# rigidPCB_rev.net
KiCad netlist of a schematic drawn in Altium Designer
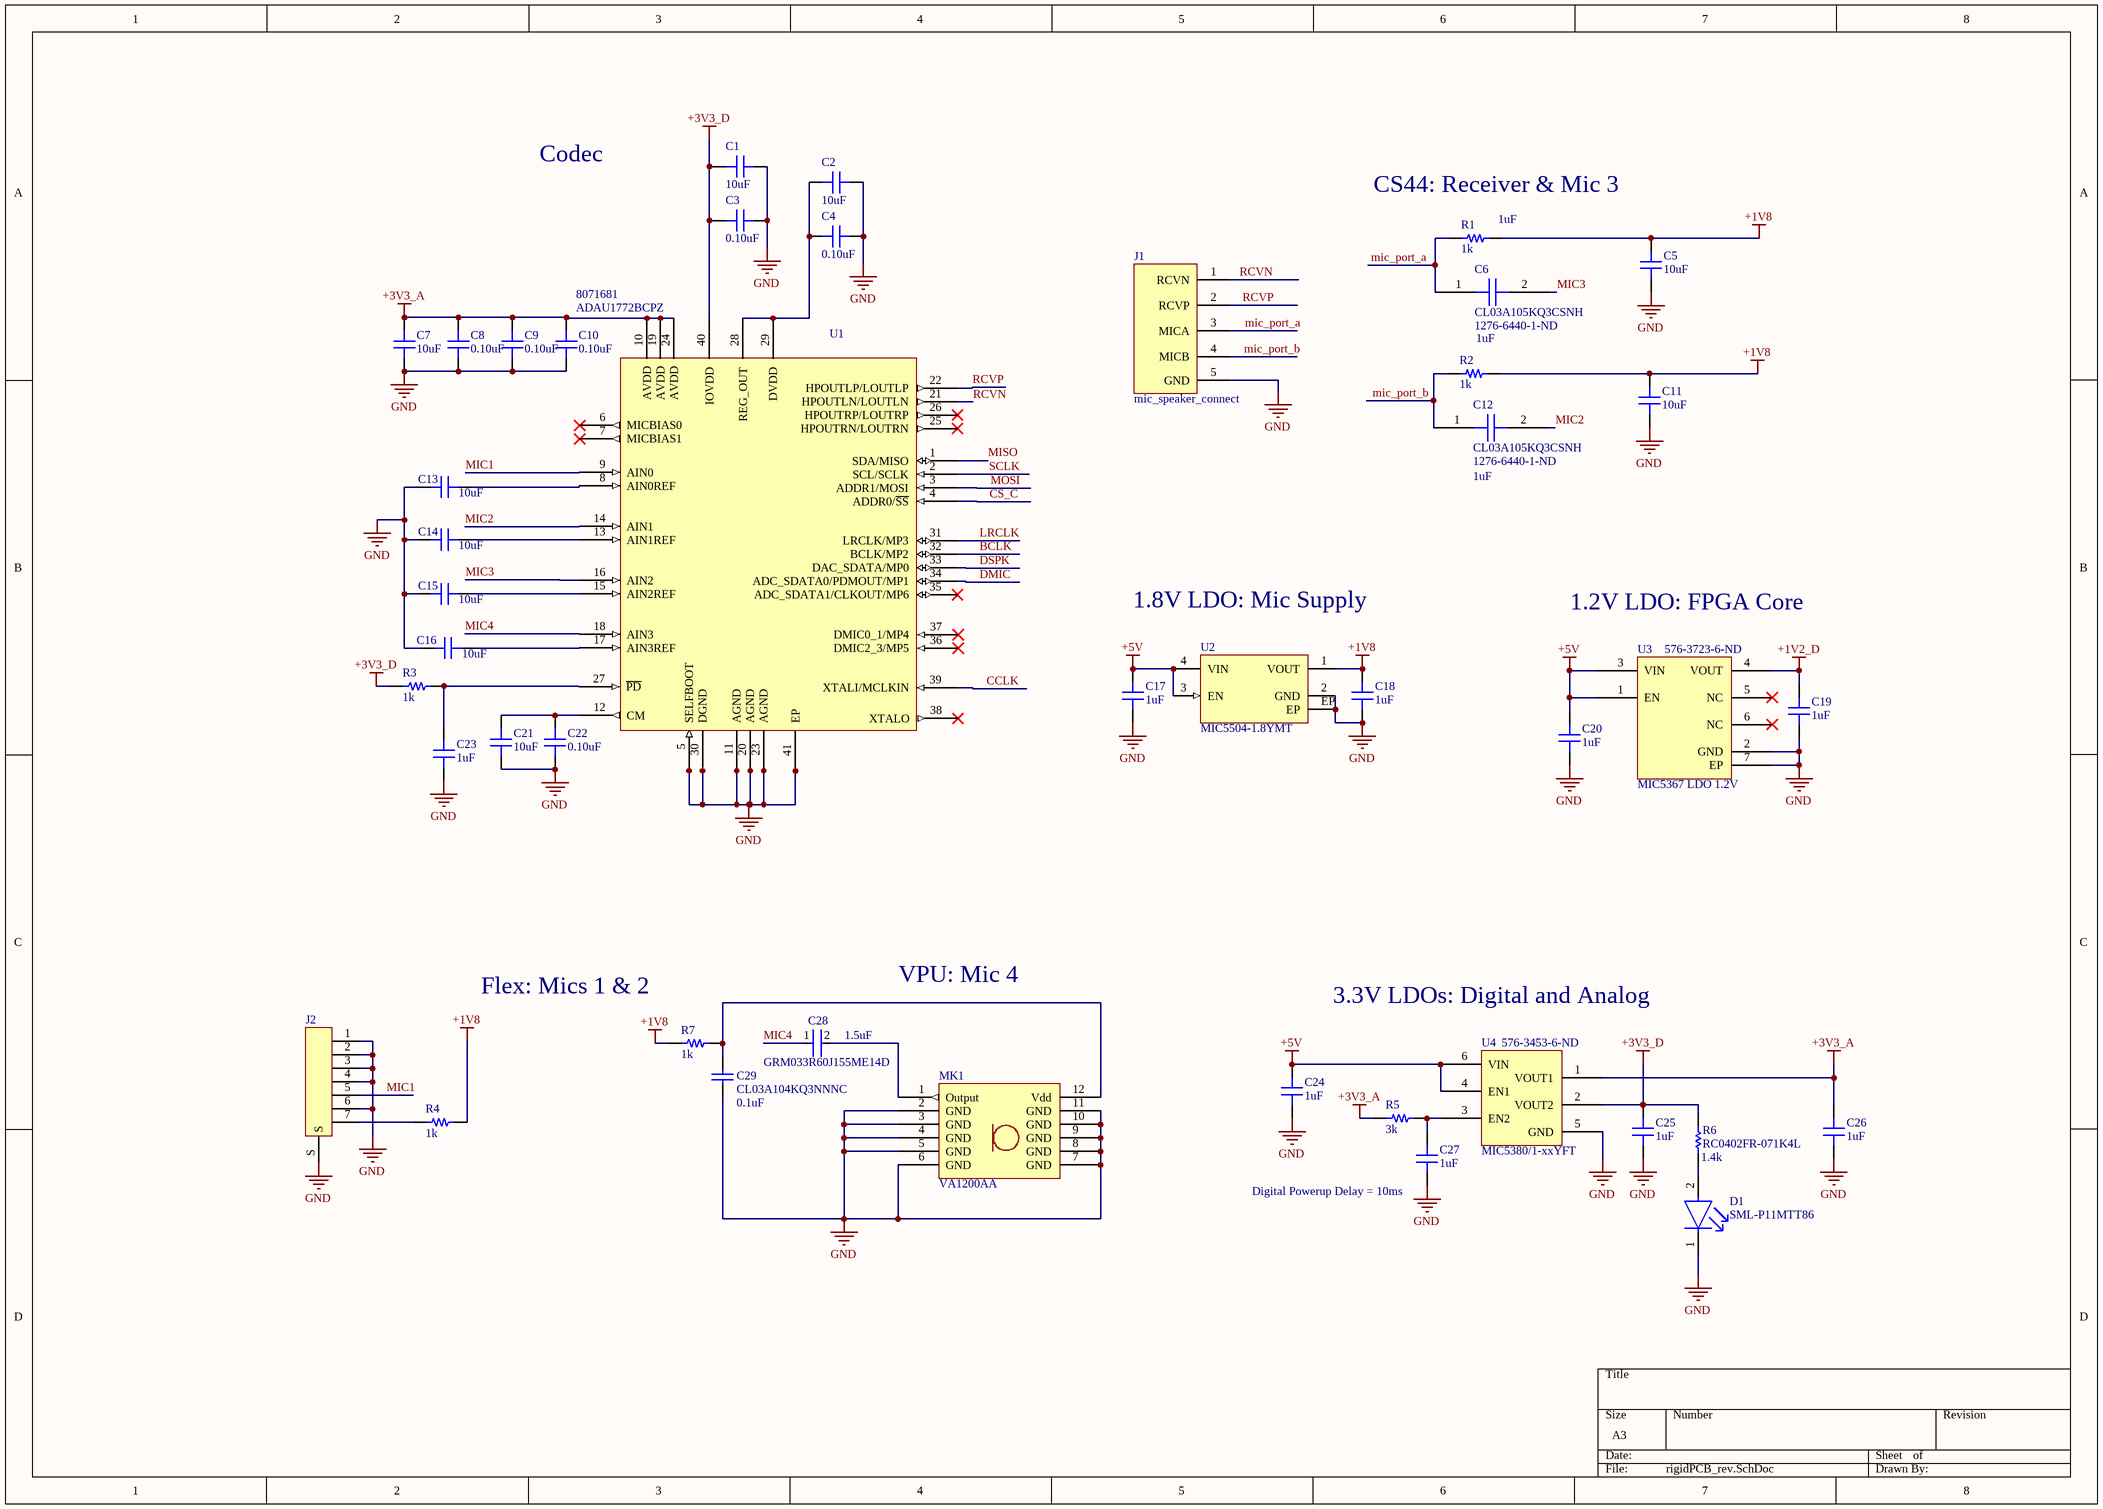
[diagram p0: rigidPCB_rev.SchDoc]

(export (version "E")
  (design (tool "Eeschema 10.0.6"))
  (components
    (comp (ref "C1")
      (value "10uF")
      (footprint "CAP 0402/1005")
      (description "CAP CER 10UF 6.3V X5R 0402")
      (fields
        (field (name "PART NUMBER") "C1005X5R0J106M050BC")
        (field (name "MANUFACTURER") "TDK Corporation")
      )
      (libsource (lib "Celestial Library Database") (part "Capacitor"))
    )
    (comp (ref "C2")
      (value "10uF")
      (footprint "CAP 0402/1005")
      (description "CAP CER 10UF 6.3V X5R 0402")
      (fields
        (field (name "PART NUMBER") "C1005X5R0J106M050BC")
        (field (name "MANUFACTURER") "TDK Corporation")
      )
      (libsource (lib "Celestial Library Database") (part "Capacitor"))
    )
    (comp (ref "C3")
      (value "0.10uF")
      (footprint "CAP 0201/0603")
      (description "CAP CER 0.1UF 10V X5R 0201")
      (fields
        (field (name "PART NUMBER") "CL03A104KP3NNNC")
        (field (name "MANUFACTURER") "Samsung Electro-Mechanics America, Inc.")
      )
      (libsource (lib "Celestial Library Database") (part "Capacitor"))
    )
    (comp (ref "C4")
      (value "0.10uF")
      (footprint "CAP 0201/0603")
      (description "CAP CER 0.1UF 10V X5R 0201")
      (fields
        (field (name "PART NUMBER") "CL03A104KP3NNNC")
        (field (name "MANUFACTURER") "Samsung Electro-Mechanics America, Inc.")
      )
      (libsource (lib "Celestial Library Database") (part "Capacitor"))
    )
    (comp (ref "C5")
      (value "10uF")
      (footprint "CAP 0402/1005")
      (description "CAP CER 10UF 6.3V X5R 0402")
      (fields
        (field (name "PART NUMBER") "C1005X5R0J106M050BC")
        (field (name "MANUFACTURER") "TDK Corporation")
      )
      (libsource (lib "Celestial Library Database") (part "Capacitor"))
    )
    (comp (ref "C6")
      (value "CL03A105KQ3CSNH")
      (footprint "CL03A105KQ3CSNH")
      (description "1 µF ±10% 6.3V Ceramic Capacitor X5R 0201 (0603 Metric)")
      (fields (field (name "SUPPLIER PART NUMBER 1") "1276-6440-1-ND"))
      (libsource (lib "OSP_DJB_Rigid") (part "CL03A105KQ3CSNH"))
    )
    (comp (ref "C7")
      (value "10uF")
      (footprint "CAP 0402/1005")
      (description "CAP CER 10UF 6.3V X5R 0402")
      (fields
        (field (name "PART NUMBER") "C1005X5R0J106M050BC")
        (field (name "MANUFACTURER") "TDK Corporation")
      )
      (libsource (lib "Celestial Library Database") (part "Capacitor"))
    )
    (comp (ref "C8")
      (value "0.10uF")
      (footprint "CAP 0201/0603")
      (description "CAP CER 0.1UF 10V X5R 0201")
      (fields
        (field (name "PART NUMBER") "CL03A104KP3NNNC")
        (field (name "MANUFACTURER") "Samsung Electro-Mechanics America, Inc.")
      )
      (libsource (lib "Celestial Library Database") (part "Capacitor"))
    )
    (comp (ref "C9")
      (value "0.10uF")
      (footprint "CAP 0201/0603")
      (description "CAP CER 0.1UF 10V X5R 0201")
      (fields
        (field (name "PART NUMBER") "CL03A104KP3NNNC")
        (field (name "MANUFACTURER") "Samsung Electro-Mechanics America, Inc.")
      )
      (libsource (lib "Celestial Library Database") (part "Capacitor"))
    )
    (comp (ref "C10")
      (value "0.10uF")
      (footprint "CAP 0201/0603")
      (description "CAP CER 0.1UF 10V X5R 0201")
      (fields
        (field (name "PART NUMBER") "CL03A104KP3NNNC")
        (field (name "MANUFACTURER") "Samsung Electro-Mechanics America, Inc.")
      )
      (libsource (lib "Celestial Library Database") (part "Capacitor"))
    )
    (comp (ref "C11")
      (value "10uF")
      (footprint "CAP 0402/1005")
      (description "CAP CER 10UF 6.3V X5R 0402")
      (fields
        (field (name "PART NUMBER") "C1005X5R0J106M050BC")
        (field (name "MANUFACTURER") "TDK Corporation")
      )
      (libsource (lib "Celestial Library Database") (part "Capacitor"))
    )
    (comp (ref "C12")
      (value "CL03A105KQ3CSNH")
      (footprint "CL03A105KQ3CSNH")
      (description "1 µF ±10% 6.3V Ceramic Capacitor X5R 0201 (0603 Metric)")
      (fields (field (name "SUPPLIER PART NUMBER 1") "1276-6440-1-ND"))
      (libsource (lib "OSP_DJB_Rigid") (part "CL03A105KQ3CSNH"))
    )
    (comp (ref "C13")
      (value "10uF")
      (footprint "CAP 0402/1005")
      (description "CAP CER 10UF 6.3V X5R 0402")
      (fields
        (field (name "PART NUMBER") "C1005X5R0J106M050BC")
        (field (name "MANUFACTURER") "TDK Corporation")
      )
      (libsource (lib "Celestial Library Database") (part "Capacitor"))
    )
    (comp (ref "C14")
      (value "10uF")
      (footprint "CAP 0402/1005")
      (description "CAP CER 10UF 6.3V X5R 0402")
      (fields
        (field (name "PART NUMBER") "C1005X5R0J106M050BC")
        (field (name "MANUFACTURER") "TDK Corporation")
      )
      (libsource (lib "Celestial Library Database") (part "Capacitor"))
    )
    (comp (ref "C15")
      (value "10uF")
      (footprint "CAP 0402/1005")
      (description "CAP CER 10UF 6.3V X5R 0402")
      (fields
        (field (name "PART NUMBER") "C1005X5R0J106M050BC")
        (field (name "MANUFACTURER") "TDK Corporation")
      )
      (libsource (lib "Celestial Library Database") (part "Capacitor"))
    )
    (comp (ref "C16")
      (value "10uF")
      (footprint "CAP 0402/1005")
      (description "CAP CER 10UF 6.3V X5R 0402")
      (fields
        (field (name "PART NUMBER") "C1005X5R0J106M050BC")
        (field (name "MANUFACTURER") "TDK Corporation")
      )
      (libsource (lib "Celestial Library Database") (part "Capacitor"))
    )
    (comp (ref "C17")
      (value "1uF")
      (footprint "CAP 0201/0603")
      (description "CAP CER 1UF 6.3V X5R 0201")
      (fields (field (name "PART NUMBER") "02016D105MAT2A") (field (name "MANUFACTURER") "AVX Corporation"))
      (libsource (lib "Celestial Library Database") (part "Capacitor"))
    )
    (comp (ref "C18")
      (value "1uF")
      (footprint "CAP 0201/0603")
      (description "CAP CER 1UF 6.3V X5R 0201")
      (fields (field (name "PART NUMBER") "02016D105MAT2A") (field (name "MANUFACTURER") "AVX Corporation"))
      (libsource (lib "Celestial Library Database") (part "Capacitor"))
    )
    (comp (ref "C19")
      (value "1uF")
      (footprint "CAP 0201/0603")
      (description "CAP CER 1UF 6.3V X5R 0201")
      (fields (field (name "PART NUMBER") "02016D105MAT2A") (field (name "MANUFACTURER") "AVX Corporation"))
      (libsource (lib "Celestial Library Database") (part "Capacitor"))
    )
    (comp (ref "C20")
      (value "1uF")
      (footprint "CAP 0201/0603")
      (description "CAP CER 1UF 6.3V X5R 0201")
      (fields (field (name "PART NUMBER") "02016D105MAT2A") (field (name "MANUFACTURER") "AVX Corporation"))
      (libsource (lib "Celestial Library Database") (part "Capacitor"))
    )
    (comp (ref "C21")
      (value "10uF")
      (footprint "CAP 0402/1005")
      (description "CAP CER 10UF 6.3V X5R 0402")
      (fields
        (field (name "PART NUMBER") "C1005X5R0J106M050BC")
        (field (name "MANUFACTURER") "TDK Corporation")
      )
      (libsource (lib "Celestial Library Database") (part "Capacitor"))
    )
    (comp (ref "C22")
      (value "0.10uF")
      (footprint "CAP 0201/0603")
      (description "CAP CER 0.1UF 10V X5R 0201")
      (fields
        (field (name "PART NUMBER") "CL03A104KP3NNNC")
        (field (name "MANUFACTURER") "Samsung Electro-Mechanics America, Inc.")
      )
      (libsource (lib "Celestial Library Database") (part "Capacitor"))
    )
    (comp (ref "C23")
      (value "1uF")
      (footprint "CAP 0201/0603")
      (description "CAP CER 1UF 6.3V X5R 0201")
      (fields (field (name "PART NUMBER") "02016D105MAT2A") (field (name "MANUFACTURER") "AVX Corporation"))
      (libsource (lib "Celestial Library Database") (part "Capacitor"))
    )
    (comp (ref "C24")
      (value "1uF")
      (footprint "CAP 0201/0603")
      (description "CAP CER 1UF 6.3V X5R 0201")
      (fields (field (name "PART NUMBER") "02016D105MAT2A") (field (name "MANUFACTURER") "AVX Corporation"))
      (libsource (lib "Celestial Library Database") (part "Capacitor"))
    )
    (comp (ref "C25")
      (value "1uF")
      (footprint "CAP 0201/0603")
      (description "CAP CER 1UF 6.3V X5R 0201")
      (fields (field (name "PART NUMBER") "02016D105MAT2A") (field (name "MANUFACTURER") "AVX Corporation"))
      (libsource (lib "Celestial Library Database") (part "Capacitor"))
    )
    (comp (ref "C26")
      (value "1uF")
      (footprint "CAP 0201/0603")
      (description "CAP CER 1UF 6.3V X5R 0201")
      (fields (field (name "PART NUMBER") "02016D105MAT2A") (field (name "MANUFACTURER") "AVX Corporation"))
      (libsource (lib "Celestial Library Database") (part "Capacitor"))
    )
    (comp (ref "C27")
      (value "1uF")
      (footprint "CAP 0201/0603")
      (description "CAP CER 1UF 6.3V X5R 0201")
      (fields (field (name "PART NUMBER") "02016D105MAT2A") (field (name "MANUFACTURER") "AVX Corporation"))
      (libsource (lib "Celestial Library Database") (part "Capacitor"))
    )
    (comp (ref "C28")
      (value "GRM033R60J155ME14D")
      (footprint "FP-GRM033-0_03-IPC_B")
      (description "Chip Multilayer Ceramic Capacitors for General Purpose, 0201, 1.5uF, X5R, 15%, 20%, 6.3V")
      (fields (field (name "TOLERANCE") "20%"))
      (libsource (lib "Altium Content Vault") (part "b4654b650e69147ec39a6b967a45e02"))
    )
    (comp (ref "C29")
      (value "CL03A104KQ3NNNC")
      (footprint "CAPC0603X33X15ML03T05")
      (fields (field (name "MANUFACTURER") "Samsung"))
      (libsource (lib "Altium Content Vault") (part "CAP"))
    )
    (comp (ref "D1")
      (value "SML-P11MTT86")
      (footprint "FP-SML-P11MTT86-MFG")
      (description "LED YELLOW/GREEN CLEAR 1006 SMD")
      (libsource (lib "Altium Content Vault") (part "8706943c75ba83719d021d2fdc84c58"))
    )
    (comp (ref "J1")
      (value "mic_speaker_connect")
      (description "connector to integrated microphone and speaker")
      (libsource (lib "OSP_DJB_Rigid") (part "mic_speaker_connect"))
    )
    (comp (ref "J2")
      (value "FFC")
      (footprint "HIROSE_FH58M-7S-0.25SHW-99")
      (description "Hirose FH58M-7S-0.25SHW(99) 7-pin Top+Bottom Contact FFC Connector")
      (libsource (lib "OSP_Symbols") (part "HIROSE_FH58M-7S-0.25SHW-99"))
    )
    (comp (ref "MK1")
      (value "VA1200AA")
      (footprint "VA1200AA")
      (description "Bone Conductor Sensor Accelerometer")
      (libsource (lib "OSP_DJB_Rigid") (part "VA1200AA"))
    )
    (comp (ref "R1")
      (value "1k")
      (footprint "RES 0201/0603")
      (description "RES SMD 1K OHM 5% 1/20W 0201")
      (fields (field (name "PART NUMBER") "RC0201JR-071KL") (field (name "MANUFACTURER") "Yageo"))
      (libsource (lib "Celestial Library Database") (part "Resistor"))
    )
    (comp (ref "R2")
      (value "1k")
      (footprint "RES 0201/0603")
      (description "RES SMD 1K OHM 5% 1/20W 0201")
      (fields (field (name "PART NUMBER") "RC0201JR-071KL") (field (name "MANUFACTURER") "Yageo"))
      (libsource (lib "Celestial Library Database") (part "Resistor"))
    )
    (comp (ref "R3")
      (value "1k")
      (footprint "RES 0201/0603")
      (description "RES SMD 1K OHM 5% 1/20W 0201")
      (fields (field (name "PART NUMBER") "RC0201JR-071KL") (field (name "MANUFACTURER") "Yageo"))
      (libsource (lib "Celestial Library Database") (part "Resistor"))
    )
    (comp (ref "R4")
      (value "1k")
      (footprint "RES 0201/0603")
      (description "RES SMD 1K OHM 5% 1/20W 0201")
      (fields (field (name "PART NUMBER") "RC0201JR-071KL") (field (name "MANUFACTURER") "Yageo"))
      (libsource (lib "Celestial Library Database") (part "Resistor"))
    )
    (comp (ref "R5")
      (value "3k")
      (footprint "RES 0201/0603")
      (description "RES SMD 3K OHM 1% 1/20W 0201")
      (fields (field (name "PART NUMBER") "RC0201FR-073KL") (field (name "MANUFACTURER") "Yageo"))
      (libsource (lib "Celestial Library Database") (part "Resistor"))
    )
    (comp (ref "R6")
      (value "RC0402FR-071K4L")
      (footprint "RESC1005X40X25NL05T10")
      (fields (field (name "MANUFACTURER") "Yageo / Phycomp"))
      (libsource (lib "Altium Content Vault") (part "RES"))
    )
    (comp (ref "R7")
      (value "1k")
      (footprint "RES 0201/0603")
      (description "RES SMD 1K OHM 5% 1/20W 0201")
      (fields (field (name "PART NUMBER") "RC0201JR-071KL") (field (name "MANUFACTURER") "Yageo"))
      (libsource (lib "Celestial Library Database") (part "Resistor"))
    )
    (comp (ref "U1")
      (value "~")
      (footprint "ADAU1772BCPZ")
      (description "General Purpose Audio Codec 4ADC / 2DAC Ch 40-Pin LFCSP")
      (fields
        (field (name "SUPPLIER PART NUMBER 1") "ADAU1772BCPZ")
        (field (name "SUPPLIER PART NUMBER 2") "8071681")
      )
      (libsource (lib "OSP_DJB_Rigid") (part "ADAU1772BCPZ"))
    )
    (comp (ref "U2")
      (value "MIC5504-1.8YMT")
      (footprint "MICREL_DFN4")
      (description "Micrel MIC5504-1.8YMT 1.8V 300mA LDO")
      (libsource (lib "OSP_Symbols") (part "MICREL_MIC5504-1.8YMT"))
    )
    (comp (ref "U3")
      (value "MIC5367 LDO 1.2V")
      (footprint "LDO 1.2V")
      (fields (field (name "SUPPLIER PART NUMBER 1") "576-3723-6-ND"))
      (libsource (lib "Mark_Library1") (part "MIC5367 LDO 1.2V"))
    )
    (comp (ref "U4")
      (value "MIC5380/1-xxYFT")
      (footprint "06L FCSTSLP")
      (description "LDO 2fixed Outputs")
      (fields (field (name "SUPPLIER PART NUMBER 1") "576-3453-6-ND"))
      (libsource (lib "Mark_Library1") (part "MIC5380/1-xxYFT"))
    )
  )
  (nets
    (net (code "1") (name "+1V2_D") (class "Default")
      (node (ref "C19") (pin "2") (pinfunction "2_2") (pintype "passive"))
      (node (ref "U3") (pin "4") (pinfunction "VOUT_4") (pintype "passive"))
    )
    (net (code "2") (name "+1V8") (class "Default")
      (node (ref "C11") (pin "2") (pinfunction "2_2") (pintype "passive"))
      (node (ref "C18") (pin "2") (pinfunction "2_2") (pintype "passive"))
      (node (ref "C5") (pin "2") (pinfunction "2_2") (pintype "passive"))
      (node (ref "R1") (pin "2") (pinfunction "2_2") (pintype "passive"))
      (node (ref "R2") (pin "2") (pinfunction "2_2") (pintype "passive"))
      (node (ref "R4") (pin "2") (pinfunction "2_2") (pintype "passive"))
      (node (ref "R7") (pin "1") (pinfunction "1_1") (pintype "passive"))
      (node (ref "U2") (pin "1") (pinfunction "VOUT_1") (pintype "power_in"))
    )
    (net (code "3") (name "+3V3_A") (class "Default")
      (node (ref "C10") (pin "2") (pinfunction "2_2") (pintype "passive"))
      (node (ref "C26") (pin "2") (pinfunction "2_2") (pintype "passive"))
      (node (ref "C7") (pin "1") (pinfunction "1_1") (pintype "passive"))
      (node (ref "C8") (pin "2") (pinfunction "2_2") (pintype "passive"))
      (node (ref "C9") (pin "2") (pinfunction "2_2") (pintype "passive"))
      (node (ref "R5") (pin "1") (pinfunction "1_1") (pintype "passive"))
      (node (ref "U1") (pin "10") (pinfunction "AVDD_10") (pintype "power_in"))
      (node (ref "U1") (pin "19") (pinfunction "AVDD_19") (pintype "power_in"))
      (node (ref "U1") (pin "24") (pinfunction "AVDD_24") (pintype "power_in"))
      (node (ref "U4") (pin "1") (pinfunction "VOUT1_1") (pintype "passive"))
    )
    (net (code "4") (name "+3V3_D") (class "Default")
      (node (ref "C1") (pin "2") (pinfunction "2_2") (pintype "passive"))
      (node (ref "C25") (pin "2") (pinfunction "2_2") (pintype "passive"))
      (node (ref "C3") (pin "1") (pinfunction "1_1") (pintype "passive"))
      (node (ref "R3") (pin "1") (pinfunction "1_1") (pintype "passive"))
      (node (ref "R6") (pin "2") (pinfunction "2_2") (pintype "passive"))
      (node (ref "U1") (pin "40") (pinfunction "IOVDD_40") (pintype "power_in"))
      (node (ref "U4") (pin "2") (pinfunction "VOUT2_2") (pintype "passive"))
    )
    (net (code "5") (name "+5V") (class "Default")
      (node (ref "C17") (pin "2") (pinfunction "2_2") (pintype "passive"))
      (node (ref "C20") (pin "2") (pinfunction "2_2") (pintype "passive"))
      (node (ref "C24") (pin "2") (pinfunction "2_2") (pintype "passive"))
      (node (ref "U2") (pin "3") (pinfunction "EN_3") (pintype "input"))
      (node (ref "U2") (pin "4") (pinfunction "VIN_4") (pintype "power_in"))
      (node (ref "U3") (pin "1") (pinfunction "EN_1") (pintype "passive"))
      (node (ref "U3") (pin "3") (pinfunction "VIN_3") (pintype "passive"))
      (node (ref "U4") (pin "4") (pinfunction "EN1_4") (pintype "passive"))
      (node (ref "U4") (pin "6") (pinfunction "VIN_6") (pintype "passive"))
    )
    (net (code "6") (name "/BCLK") (class "Default")
      (node (ref "U1") (pin "32") (pinfunction "BCLK/MP2_32") (pintype "bidirectional"))
    )
    (net (code "7") (name "/CCLK") (class "Default")
      (node (ref "U1") (pin "39") (pinfunction "XTALI/MCLKIN_39") (pintype "input"))
    )
    (net (code "8") (name "/CS_C") (class "Default")
      (node (ref "U1") (pin "4") (pinfunction "ADDR0/~{SS}_4") (pintype "input"))
    )
    (net (code "9") (name "/DMIC") (class "Default")
      (node (ref "U1") (pin "34") (pinfunction "ADC_SDATA0/PDMOUT/MP1_34") (pintype "bidirectional"))
    )
    (net (code "10") (name "/DSPK") (class "Default")
      (node (ref "U1") (pin "33") (pinfunction "DAC_SDATA/MP0_33") (pintype "bidirectional"))
    )
    (net (code "11") (name "/LRCLK") (class "Default")
      (node (ref "U1") (pin "31") (pinfunction "LRCLK/MP3_31") (pintype "bidirectional"))
    )
    (net (code "12") (name "/MIC1") (class "Default")
      (node (ref "J2") (pin "5") (pintype "passive"))
      (node (ref "U1") (pin "9") (pinfunction "AIN0_9") (pintype "input"))
    )
    (net (code "13") (name "/MIC2") (class "Default")
      (node (ref "C12") (pin "2") (pinfunction "2_2") (pintype "passive"))
      (node (ref "U1") (pin "14") (pinfunction "AIN1_14") (pintype "input"))
    )
    (net (code "14") (name "/MIC3") (class "Default")
      (node (ref "C6") (pin "2") (pinfunction "2_2") (pintype "passive"))
      (node (ref "U1") (pin "16") (pinfunction "AIN2_16") (pintype "input"))
    )
    (net (code "15") (name "/MIC4") (class "Default")
      (node (ref "C28") (pin "1") (pinfunction "1_1") (pintype "passive"))
      (node (ref "U1") (pin "18") (pinfunction "AIN3_18") (pintype "input"))
    )
    (net (code "16") (name "/MISO") (class "Default")
      (node (ref "U1") (pin "1") (pinfunction "SDA/MISO_1") (pintype "bidirectional"))
    )
    (net (code "17") (name "/MOSI") (class "Default")
      (node (ref "U1") (pin "3") (pinfunction "ADDR1/MOSI_3") (pintype "input"))
    )
    (net (code "18") (name "/RCVN") (class "Default")
      (node (ref "J1") (pin "1") (pinfunction "RCVN_1") (pintype "passive"))
      (node (ref "U1") (pin "21") (pinfunction "HPOUTLN/LOUTLN_21") (pintype "output"))
    )
    (net (code "19") (name "/RCVP") (class "Default")
      (node (ref "J1") (pin "2") (pinfunction "RCVP_2") (pintype "passive"))
      (node (ref "U1") (pin "22") (pinfunction "HPOUTLP/LOUTLP_22") (pintype "output"))
    )
    (net (code "20") (name "/SCLK") (class "Default")
      (node (ref "U1") (pin "2") (pinfunction "SCL/SCLK_2") (pintype "input"))
    )
    (net (code "21") (name "/mic_port_a") (class "Default")
      (node (ref "C6") (pin "1") (pinfunction "1_1") (pintype "passive"))
      (node (ref "J1") (pin "3") (pinfunction "MICA_3") (pintype "passive"))
      (node (ref "R1") (pin "1") (pinfunction "1_1") (pintype "passive"))
    )
    (net (code "22") (name "/mic_port_b") (class "Default")
      (node (ref "C12") (pin "1") (pinfunction "1_1") (pintype "passive"))
      (node (ref "J1") (pin "4") (pinfunction "MICB_4") (pintype "passive"))
      (node (ref "R2") (pin "1") (pinfunction "1_1") (pintype "passive"))
    )
    (net (code "23") (name "GND") (class "Default")
      (node (ref "C1") (pin "1") (pinfunction "1_1") (pintype "passive"))
      (node (ref "C10") (pin "1") (pinfunction "1_1") (pintype "passive"))
      (node (ref "C11") (pin "1") (pinfunction "1_1") (pintype "passive"))
      (node (ref "C13") (pin "2") (pinfunction "2_2") (pintype "passive"))
      (node (ref "C14") (pin "2") (pinfunction "2_2") (pintype "passive"))
      (node (ref "C15") (pin "2") (pinfunction "2_2") (pintype "passive"))
      (node (ref "C16") (pin "2") (pinfunction "2_2") (pintype "passive"))
      (node (ref "C17") (pin "1") (pinfunction "1_1") (pintype "passive"))
      (node (ref "C18") (pin "1") (pinfunction "1_1") (pintype "passive"))
      (node (ref "C19") (pin "1") (pinfunction "1_1") (pintype "passive"))
      (node (ref "C2") (pin "1") (pinfunction "1_1") (pintype "passive"))
      (node (ref "C20") (pin "1") (pinfunction "1_1") (pintype "passive"))
      (node (ref "C21") (pin "2") (pinfunction "2_2") (pintype "passive"))
      (node (ref "C22") (pin "1") (pinfunction "1_1") (pintype "passive"))
      (node (ref "C23") (pin "1") (pinfunction "1_1") (pintype "passive"))
      (node (ref "C24") (pin "1") (pinfunction "1_1") (pintype "passive"))
      (node (ref "C25") (pin "1") (pinfunction "1_1") (pintype "passive"))
      (node (ref "C26") (pin "1") (pinfunction "1_1") (pintype "passive"))
      (node (ref "C27") (pin "1") (pinfunction "1_1") (pintype "passive"))
      (node (ref "C29") (pin "1") (pinfunction "1_1") (pintype "passive"))
      (node (ref "C3") (pin "2") (pinfunction "2_2") (pintype "passive"))
      (node (ref "C4") (pin "2") (pinfunction "2_2") (pintype "passive"))
      (node (ref "C5") (pin "1") (pinfunction "1_1") (pintype "passive"))
      (node (ref "C7") (pin "2") (pinfunction "2_2") (pintype "passive"))
      (node (ref "C8") (pin "1") (pinfunction "1_1") (pintype "passive"))
      (node (ref "C9") (pin "1") (pinfunction "1_1") (pintype "passive"))
      (node (ref "D1") (pin "1") (pinfunction "C_1") (pintype "passive"))
      (node (ref "J1") (pin "5") (pinfunction "GND_5") (pintype "passive"))
      (node (ref "J2") (pin "1") (pintype "passive"))
      (node (ref "J2") (pin "2") (pintype "passive"))
      (node (ref "J2") (pin "3") (pintype "passive"))
      (node (ref "J2") (pin "4") (pintype "passive"))
      (node (ref "J2") (pin "6") (pintype "passive"))
      (node (ref "J2") (pin "S") (pinfunction "S_S") (pintype "power_in"))
      (node (ref "MK1") (pin "10") (pinfunction "GND_10") (pintype "power_in"))
      (node (ref "MK1") (pin "11") (pinfunction "GND_11") (pintype "power_in"))
      (node (ref "MK1") (pin "2") (pinfunction "GND_2") (pintype "power_in"))
      (node (ref "MK1") (pin "3") (pinfunction "GND_3") (pintype "power_in"))
      (node (ref "MK1") (pin "4") (pinfunction "GND_4") (pintype "power_in"))
      (node (ref "MK1") (pin "5") (pinfunction "GND_5") (pintype "power_in"))
      (node (ref "MK1") (pin "6") (pinfunction "GND_6") (pintype "power_in"))
      (node (ref "MK1") (pin "7") (pinfunction "GND_7") (pintype "power_in"))
      (node (ref "MK1") (pin "8") (pinfunction "GND_8") (pintype "power_in"))
      (node (ref "MK1") (pin "9") (pinfunction "GND_9") (pintype "power_in"))
      (node (ref "U1") (pin "11") (pinfunction "AGND_11") (pintype "power_in"))
      (node (ref "U1") (pin "20") (pinfunction "AGND_20") (pintype "power_in"))
      (node (ref "U1") (pin "23") (pinfunction "AGND_23") (pintype "power_in"))
      (node (ref "U1") (pin "30") (pinfunction "DGND_30") (pintype "power_in"))
      (node (ref "U1") (pin "41") (pinfunction "EP_41") (pintype "passive"))
      (node (ref "U1") (pin "5") (pinfunction "SELFBOOT_5") (pintype "input"))
      (node (ref "U2") (pin "2") (pinfunction "GND_2") (pintype "power_in"))
      (node (ref "U2") (pin "EP") (pinfunction "EP_EP") (pintype "power_in"))
      (node (ref "U3") (pin "2") (pinfunction "GND_2") (pintype "passive"))
      (node (ref "U3") (pin "7") (pinfunction "EP_7") (pintype "passive"))
      (node (ref "U4") (pin "5") (pinfunction "GND_5") (pintype "passive"))
    )
    (net (code "24") (name "Net-(D1-A)") (class "Default")
      (node (ref "D1") (pin "2") (pinfunction "A_2") (pintype "passive"))
      (node (ref "R6") (pin "1") (pinfunction "1_1") (pintype "passive"))
    )
    (net (code "25") (name "Net-(J2-Pad7)") (class "Default")
      (node (ref "J2") (pin "7") (pintype "passive"))
      (node (ref "R4") (pin "1") (pinfunction "1_1") (pintype "passive"))
    )
    (net (code "26") (name "Net-(MK1-Output)") (class "Default")
      (node (ref "C28") (pin "2") (pinfunction "2_2") (pintype "passive"))
      (node (ref "MK1") (pin "1") (pinfunction "Output_1") (pintype "output"))
    )
    (net (code "27") (name "Net-(MK1-Vdd)") (class "Default")
      (node (ref "C29") (pin "2") (pinfunction "2_2") (pintype "passive"))
      (node (ref "MK1") (pin "12") (pinfunction "Vdd_12") (pintype "power_in"))
      (node (ref "R7") (pin "2") (pinfunction "2_2") (pintype "passive"))
    )
    (net (code "28") (name "Net-(U1-AIN0REF)") (class "Default")
      (node (ref "C13") (pin "1") (pinfunction "1_1") (pintype "passive"))
      (node (ref "U1") (pin "8") (pinfunction "AIN0REF_8") (pintype "input"))
    )
    (net (code "29") (name "Net-(U1-AIN1REF)") (class "Default")
      (node (ref "C14") (pin "1") (pinfunction "1_1") (pintype "passive"))
      (node (ref "U1") (pin "13") (pinfunction "AIN1REF_13") (pintype "input"))
    )
    (net (code "30") (name "Net-(U1-AIN2REF)") (class "Default")
      (node (ref "C15") (pin "1") (pinfunction "1_1") (pintype "passive"))
      (node (ref "U1") (pin "15") (pinfunction "AIN2REF_15") (pintype "input"))
    )
    (net (code "31") (name "Net-(U1-AIN3REF)") (class "Default")
      (node (ref "C16") (pin "1") (pinfunction "1_1") (pintype "passive"))
      (node (ref "U1") (pin "17") (pinfunction "AIN3REF_17") (pintype "input"))
    )
    (net (code "32") (name "Net-(U1-CM)") (class "Default")
      (node (ref "C21") (pin "1") (pinfunction "1_1") (pintype "passive"))
      (node (ref "C22") (pin "2") (pinfunction "2_2") (pintype "passive"))
      (node (ref "U1") (pin "12") (pinfunction "CM_12") (pintype "output"))
    )
    (net (code "33") (name "Net-(U1-DVDD)") (class "Default")
      (node (ref "C2") (pin "2") (pinfunction "2_2") (pintype "passive"))
      (node (ref "C4") (pin "1") (pinfunction "1_1") (pintype "passive"))
      (node (ref "U1") (pin "28") (pinfunction "REG_OUT_28") (pintype "passive"))
      (node (ref "U1") (pin "29") (pinfunction "DVDD_29") (pintype "power_in"))
    )
    (net (code "34") (name "Net-(U1-~{PD})") (class "Default")
      (node (ref "C23") (pin "2") (pinfunction "2_2") (pintype "passive"))
      (node (ref "R3") (pin "2") (pinfunction "2_2") (pintype "passive"))
      (node (ref "U1") (pin "27") (pinfunction "~{PD}_27") (pintype "input"))
    )
    (net (code "35") (name "Net-(U4-EN2)") (class "Default")
      (node (ref "C27") (pin "2") (pinfunction "2_2") (pintype "passive"))
      (node (ref "R5") (pin "2") (pinfunction "2_2") (pintype "passive"))
      (node (ref "U4") (pin "3") (pinfunction "EN2_3") (pintype "passive"))
    )
    (net (code "36") (name "unconnected-(U1-ADC_SDATA1{slash}CLKOUT{slash}MP6-Pad35)") (class "Default")
      (node (ref "U1") (pin "35") (pinfunction "ADC_SDATA1/CLKOUT/MP6_35") (pintype "bidirectional+no_connect"))
    )
    (net (code "37") (name "unconnected-(U1-DMIC0_1{slash}MP4-Pad37)") (class "Default")
      (node (ref "U1") (pin "37") (pinfunction "DMIC0_1/MP4_37") (pintype "input+no_connect"))
    )
    (net (code "38") (name "unconnected-(U1-DMIC2_3{slash}MP5-Pad36)") (class "Default")
      (node (ref "U1") (pin "36") (pinfunction "DMIC2_3/MP5_36") (pintype "input+no_connect"))
    )
    (net (code "39") (name "unconnected-(U1-HPOUTRN{slash}LOUTRN-Pad25)") (class "Default")
      (node (ref "U1") (pin "25") (pinfunction "HPOUTRN/LOUTRN_25") (pintype "output+no_connect"))
    )
    (net (code "40") (name "unconnected-(U1-HPOUTRP{slash}LOUTRP-Pad26)") (class "Default")
      (node (ref "U1") (pin "26") (pinfunction "HPOUTRP/LOUTRP_26") (pintype "output+no_connect"))
    )
    (net (code "41") (name "unconnected-(U1-MICBIAS0-Pad6)") (class "Default")
      (node (ref "U1") (pin "6") (pinfunction "MICBIAS0_6") (pintype "output"))
    )
    (net (code "42") (name "unconnected-(U1-MICBIAS1-Pad7)") (class "Default")
      (node (ref "U1") (pin "7") (pinfunction "MICBIAS1_7") (pintype "output"))
    )
    (net (code "43") (name "unconnected-(U1-XTALO-Pad38)") (class "Default")
      (node (ref "U1") (pin "38") (pinfunction "XTALO_38") (pintype "output+no_connect"))
    )
    (net (code "44") (name "unconnected-(U3-NC-Pad5)") (class "Default")
      (node (ref "U3") (pin "5") (pinfunction "NC_5") (pintype "passive+no_connect"))
    )
    (net (code "45") (name "unconnected-(U3-NC-Pad6)") (class "Default")
      (node (ref "U3") (pin "6") (pinfunction "NC_6") (pintype "passive+no_connect"))
    )
  )
)
